# recepteur.net
KiCad netlist of a schematic drawn in Altium Designer
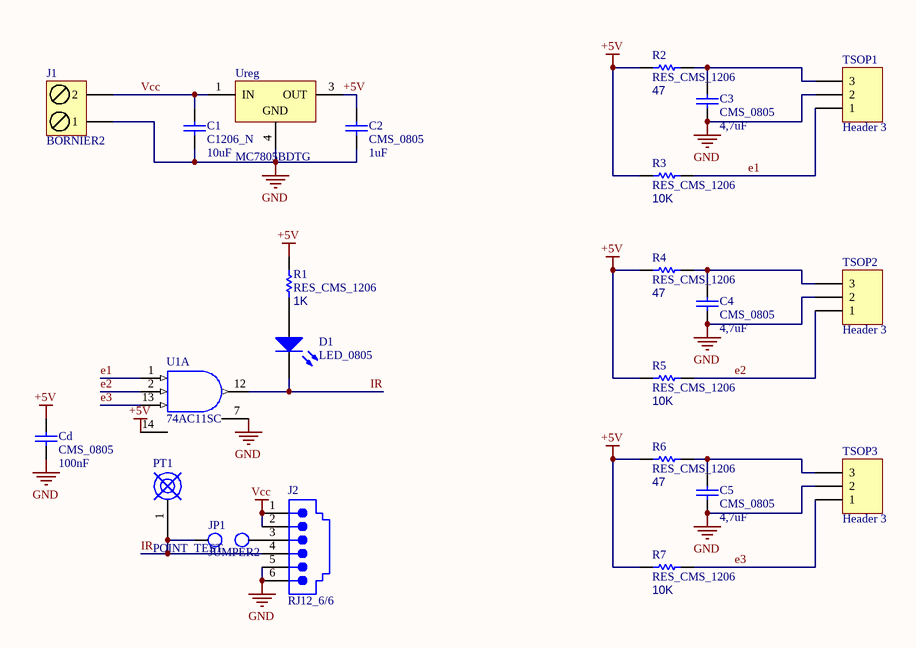
[diagram p0: recepteur.SchDoc]

(export (version "E")
  (design (tool "Eeschema 10.0.6"))
  (components
    (comp (ref "C1")
      (value "C1206_N")
      (footprint "C1206_N")
      (description "EXEMPLE_CODE FARNELL POUR 10nF : 1414662")
      (fields (field (name "ALTIUM_VALUE") "10uF"))
      (libsource (lib "projets etudiants") (part "CONDENSATEUR_CMS_0805"))
    )
    (comp (ref "C2")
      (value "CMS_0805")
      (footprint "C1206_N")
      (description "EXEMPLE_CODE FARNELL POUR 10nF : 1414662")
      (fields (field (name "ALTIUM_VALUE") "1uF"))
      (libsource (lib "projets etudiants") (part "CONDENSATEUR_CMS_0805"))
    )
    (comp (ref "C3")
      (value "CMS_0805")
      (footprint "C1206_N")
      (description "EXEMPLE_CODE FARNELL POUR 10nF : 1414662")
      (fields (field (name "ALTIUM_VALUE") "4,7uF"))
      (libsource (lib "projets etudiants") (part "CONDENSATEUR_CMS_0805"))
    )
    (comp (ref "C4")
      (value "CMS_0805")
      (footprint "C1206_N")
      (description "EXEMPLE_CODE FARNELL POUR 10nF : 1414662")
      (fields (field (name "ALTIUM_VALUE") "4,7uF"))
      (libsource (lib "projets etudiants") (part "CONDENSATEUR_CMS_0805"))
    )
    (comp (ref "C5")
      (value "CMS_0805")
      (footprint "C1206_N")
      (description "EXEMPLE_CODE FARNELL POUR 10nF : 1414662")
      (fields (field (name "ALTIUM_VALUE") "4,7uF"))
      (libsource (lib "projets etudiants") (part "CONDENSATEUR_CMS_0805"))
    )
    (comp (ref "Cd")
      (value "CMS_0805")
      (footprint "C0805_N")
      (description "EXEMPLE_CODE FARNELL POUR 10nF : 1414662")
      (fields (field (name "ALTIUM_VALUE") "100nF"))
      (libsource (lib "projets etudiants") (part "CONDENSATEUR_CMS_0805"))
    )
    (comp (ref "D1")
      (value "LED_0805")
      (footprint "LED_0805")
      (description "EXEMPLE_CODE FARNELL LED VERTE : 1519493")
      (libsource (lib "projets etudiants") (part "LED_CMS_1206"))
    )
    (comp (ref "J1")
      (value "BORNIER2")
      (footprint "BORNIER2_A_VIS")
      (description "CODE ATLANTIQUE COMPOSANTS : KVBE2")
      (libsource (lib "projets etudiants") (part "BORNIER_A_VIS_2_PLOTS"))
    )
    (comp (ref "J2")
      (value "RJ12_6/6")
      (footprint "CONNECTEUR_RJ12_6/6")
      (description "CODE ATLANTIQUE COMPOSANTS : KTRCI62")
      (libsource (lib "projets etudiants") (part "CONNECTEUR_RJ12_6/6"))
    )
    (comp (ref "JP1")
      (value "JUMPER2")
      (footprint "BARRETTE2_MAL_DROIT")
      (description "CODE ATLANTIQUE COMPOSANTS : K2B40D")
      (libsource (lib "projets etudiants") (part "JUMPER2"))
    )
    (comp (ref "PT1")
      (value "POINT_TEST")
      (footprint "POINT_TEST")
      (description "CODE ATLANTIQUE COMPOSANTS : K2B40D")
      (libsource (lib "projets etudiants") (part "POINT_TEST"))
    )
    (comp (ref "R1")
      (value "RES_CMS_1206")
      (footprint "R1206_N")
      (description "CODE ATLANTIQUE COMPOSANTS POUR 1K : R12061K")
      (fields (field (name "ALTIUM_VALUE") "1K"))
      (libsource (lib "projets etudiants") (part "RESISTANCE_CMS_1206"))
    )
    (comp (ref "R2")
      (value "RES_CMS_1206")
      (footprint "R1206_N")
      (description "CODE ATLANTIQUE COMPOSANTS POUR 1K : R12061K")
      (fields (field (name "ALTIUM_VALUE") "47"))
      (libsource (lib "projets etudiants") (part "RESISTANCE_CMS_1206"))
    )
    (comp (ref "R3")
      (value "RES_CMS_1206")
      (footprint "R1206_N")
      (description "CODE ATLANTIQUE COMPOSANTS POUR 1K : R12061K")
      (fields (field (name "ALTIUM_VALUE") "10K"))
      (libsource (lib "projets etudiants") (part "RESISTANCE_CMS_1206"))
    )
    (comp (ref "R4")
      (value "RES_CMS_1206")
      (footprint "R1206_N")
      (description "CODE ATLANTIQUE COMPOSANTS POUR 1K : R12061K")
      (fields (field (name "ALTIUM_VALUE") "47"))
      (libsource (lib "projets etudiants") (part "RESISTANCE_CMS_1206"))
    )
    (comp (ref "R5")
      (value "RES_CMS_1206")
      (footprint "R1206_N")
      (description "CODE ATLANTIQUE COMPOSANTS POUR 1K : R12061K")
      (fields (field (name "ALTIUM_VALUE") "10K"))
      (libsource (lib "projets etudiants") (part "RESISTANCE_CMS_1206"))
    )
    (comp (ref "R6")
      (value "RES_CMS_1206")
      (footprint "R1206_N")
      (description "CODE ATLANTIQUE COMPOSANTS POUR 1K : R12061K")
      (fields (field (name "ALTIUM_VALUE") "47"))
      (libsource (lib "projets etudiants") (part "RESISTANCE_CMS_1206"))
    )
    (comp (ref "R7")
      (value "RES_CMS_1206")
      (footprint "R1206_N")
      (description "CODE ATLANTIQUE COMPOSANTS POUR 1K : R12061K")
      (fields (field (name "ALTIUM_VALUE") "10K"))
      (libsource (lib "projets etudiants") (part "RESISTANCE_CMS_1206"))
    )
    (comp (ref "TSOP1")
      (value "Header 3")
      (footprint "BARRETTE3_FEM")
      (description "Header, 3-Pin")
      (fields (field (name "PUBLISHER") "Altium Limited"))
      (libsource (lib "Miscellaneous Connectors") (part "Header 3"))
    )
    (comp (ref "TSOP2")
      (value "Header 3")
      (footprint "BARRETTE3_FEM")
      (description "Header, 3-Pin")
      (fields (field (name "PUBLISHER") "Altium Limited"))
      (libsource (lib "Miscellaneous Connectors") (part "Header 3"))
    )
    (comp (ref "TSOP3")
      (value "Header 3")
      (footprint "BARRETTE3_FEM")
      (description "Header, 3-Pin")
      (fields (field (name "PUBLISHER") "Altium Limited"))
      (libsource (lib "Miscellaneous Connectors") (part "Header 3"))
    )
    (comp (ref "U1")
      (value "74AC11SC")
      (footprint "M14A_N")
      (description "Triple 3-Input AND Gate, 14-Pin SOIC, Commercial Grade")
      (fields (field (name "PUBLISHER") "Altium Limited"))
      (libsource (lib "FSC Logic Gate") (part "74AC11SC"))
    )
    (comp (ref "Ureg")
      (value "MC7805BDTG")
      (footprint "369A-13")
      (description "Three-Terminal Positive Voltage Regulator")
      (fields (field (name "PUBLISHER") "Altium Limited"))
      (libsource (lib "ON Semi Power Mgt Voltage Regulator") (part "MC7805ACD2T"))
    )
  )
  (nets
    (net (code "1") (name "+5V") (class "Default")
      (node (ref "C2") (pin "2") (pinfunction "2_2") (pintype "passive"))
      (node (ref "Cd") (pin "2") (pinfunction "2_2") (pintype "passive"))
      (node (ref "R1") (pin "2") (pinfunction "2_2") (pintype "passive"))
      (node (ref "R2") (pin "2") (pinfunction "2_2") (pintype "passive"))
      (node (ref "R3") (pin "2") (pinfunction "2_2") (pintype "passive"))
      (node (ref "R4") (pin "2") (pinfunction "2_2") (pintype "passive"))
      (node (ref "R5") (pin "2") (pinfunction "2_2") (pintype "passive"))
      (node (ref "R6") (pin "2") (pinfunction "2_2") (pintype "passive"))
      (node (ref "R7") (pin "2") (pinfunction "2_2") (pintype "passive"))
      (node (ref "U1") (pin "14") (pinfunction "VCC_14") (pintype "power_in"))
      (node (ref "Ureg") (pin "3") (pinfunction "OUT_3") (pintype "power_in"))
    )
    (net (code "2") (name "/IR") (class "Default")
      (node (ref "D1") (pin "2") (pinfunction "2_2") (pintype "passive"))
      (node (ref "J2") (pin "4") (pinfunction "4_4") (pintype "passive"))
      (node (ref "JP1") (pin "1") (pinfunction "1_1") (pintype "passive"))
      (node (ref "PT1") (pin "1") (pinfunction "1_1") (pintype "passive"))
      (node (ref "U1") (pin "12") (pinfunction "O_12") (pintype "output"))
    )
    (net (code "3") (name "/e1") (class "Default")
      (node (ref "R3") (pin "1") (pinfunction "1_1") (pintype "passive"))
      (node (ref "TSOP1") (pin "1") (pinfunction "1_1") (pintype "passive"))
      (node (ref "U1") (pin "1") (pinfunction "A_1") (pintype "input"))
    )
    (net (code "4") (name "/e2") (class "Default")
      (node (ref "R5") (pin "1") (pinfunction "1_1") (pintype "passive"))
      (node (ref "TSOP2") (pin "1") (pinfunction "1_1") (pintype "passive"))
      (node (ref "U1") (pin "2") (pinfunction "B_2") (pintype "input"))
    )
    (net (code "5") (name "/e3") (class "Default")
      (node (ref "R7") (pin "1") (pinfunction "1_1") (pintype "passive"))
      (node (ref "TSOP3") (pin "1") (pinfunction "1_1") (pintype "passive"))
      (node (ref "U1") (pin "13") (pinfunction "C_13") (pintype "input"))
    )
    (net (code "6") (name "GND") (class "Default")
      (node (ref "C1") (pin "1") (pinfunction "1_1") (pintype "passive"))
      (node (ref "C2") (pin "1") (pinfunction "1_1") (pintype "passive"))
      (node (ref "C3") (pin "1") (pinfunction "1_1") (pintype "passive"))
      (node (ref "C4") (pin "1") (pinfunction "1_1") (pintype "passive"))
      (node (ref "C5") (pin "1") (pinfunction "1_1") (pintype "passive"))
      (node (ref "Cd") (pin "1") (pinfunction "1_1") (pintype "passive"))
      (node (ref "J1") (pin "1") (pinfunction "1_1") (pintype "passive"))
      (node (ref "J2") (pin "5") (pinfunction "5_5") (pintype "passive"))
      (node (ref "J2") (pin "6") (pinfunction "6_6") (pintype "passive"))
      (node (ref "TSOP1") (pin "2") (pinfunction "2_2") (pintype "passive"))
      (node (ref "TSOP2") (pin "2") (pinfunction "2_2") (pintype "passive"))
      (node (ref "TSOP3") (pin "2") (pinfunction "2_2") (pintype "passive"))
      (node (ref "U1") (pin "7") (pinfunction "GND_7") (pintype "power_in"))
      (node (ref "Ureg") (pin "4") (pinfunction "GND_4") (pintype "power_in"))
    )
    (net (code "7") (name "Net-(C3-Pad2)") (class "Default")
      (node (ref "C3") (pin "2") (pinfunction "2_2") (pintype "passive"))
      (node (ref "R2") (pin "1") (pinfunction "1_1") (pintype "passive"))
      (node (ref "TSOP1") (pin "3") (pinfunction "3_3") (pintype "passive"))
    )
    (net (code "8") (name "Net-(C4-Pad2)") (class "Default")
      (node (ref "C4") (pin "2") (pinfunction "2_2") (pintype "passive"))
      (node (ref "R4") (pin "1") (pinfunction "1_1") (pintype "passive"))
      (node (ref "TSOP2") (pin "3") (pinfunction "3_3") (pintype "passive"))
    )
    (net (code "9") (name "Net-(C5-Pad2)") (class "Default")
      (node (ref "C5") (pin "2") (pinfunction "2_2") (pintype "passive"))
      (node (ref "R6") (pin "1") (pinfunction "1_1") (pintype "passive"))
      (node (ref "TSOP3") (pin "3") (pinfunction "3_3") (pintype "passive"))
    )
    (net (code "10") (name "Net-(D1-Pad1)") (class "Default")
      (node (ref "D1") (pin "1") (pinfunction "1_1") (pintype "passive"))
      (node (ref "R1") (pin "1") (pinfunction "1_1") (pintype "passive"))
    )
    (net (code "11") (name "Net-(J2-Pad3)") (class "Default")
      (node (ref "J2") (pin "3") (pinfunction "3_3") (pintype "passive"))
      (node (ref "JP1") (pin "2") (pinfunction "2_2") (pintype "passive"))
    )
    (net (code "12") (name "Vcc") (class "Default")
      (node (ref "C1") (pin "2") (pinfunction "2_2") (pintype "passive"))
      (node (ref "J1") (pin "2") (pinfunction "2_2") (pintype "passive"))
      (node (ref "J2") (pin "1") (pinfunction "1_1") (pintype "passive"))
      (node (ref "J2") (pin "2") (pinfunction "2_2") (pintype "passive"))
      (node (ref "Ureg") (pin "1") (pinfunction "IN_1") (pintype "power_in"))
    )
  )
)
